# module.net
KiCad netlist of a schematic drawn in EAGLE
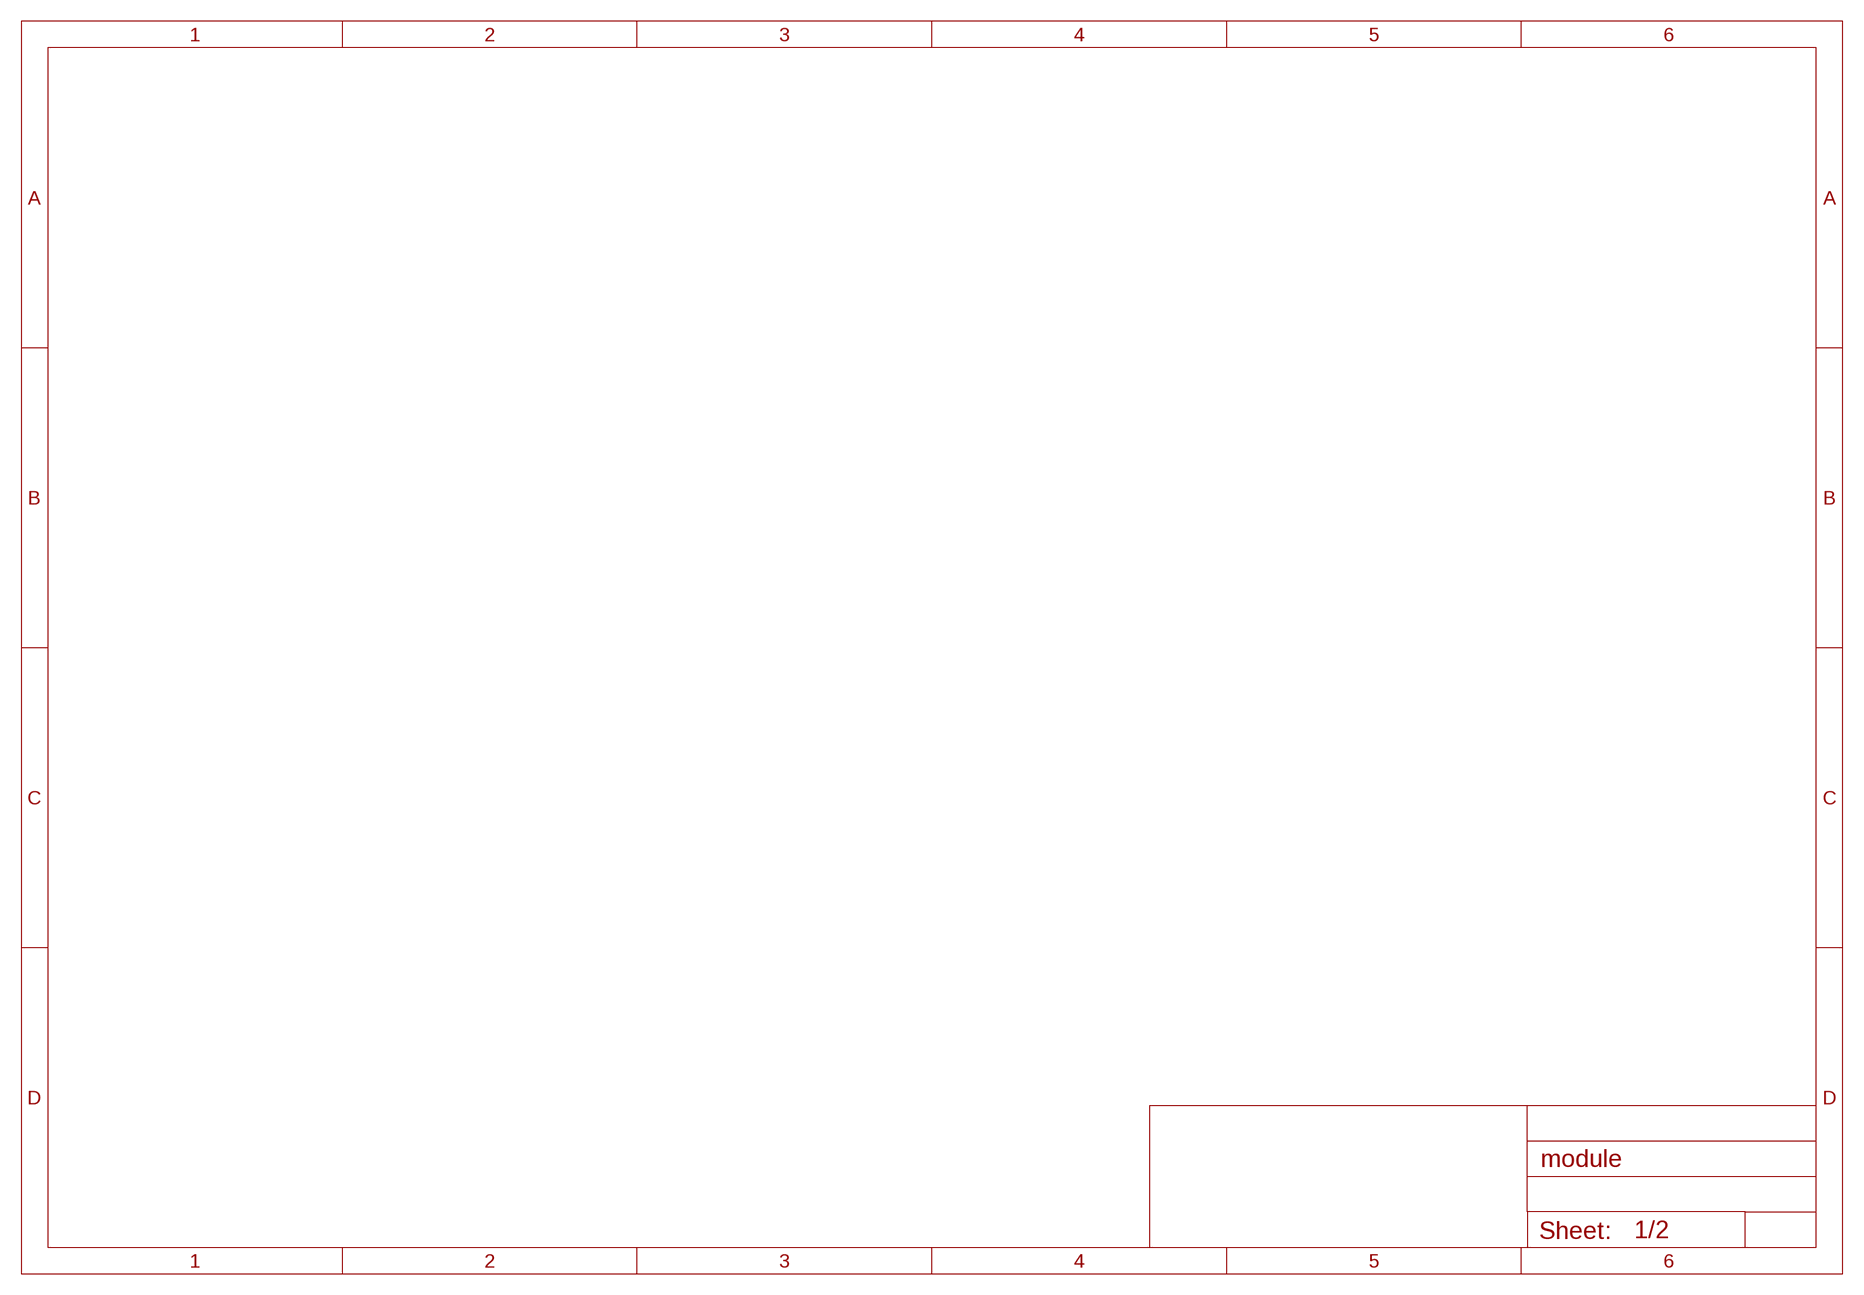
[diagram p0: schematic, sheet 1]
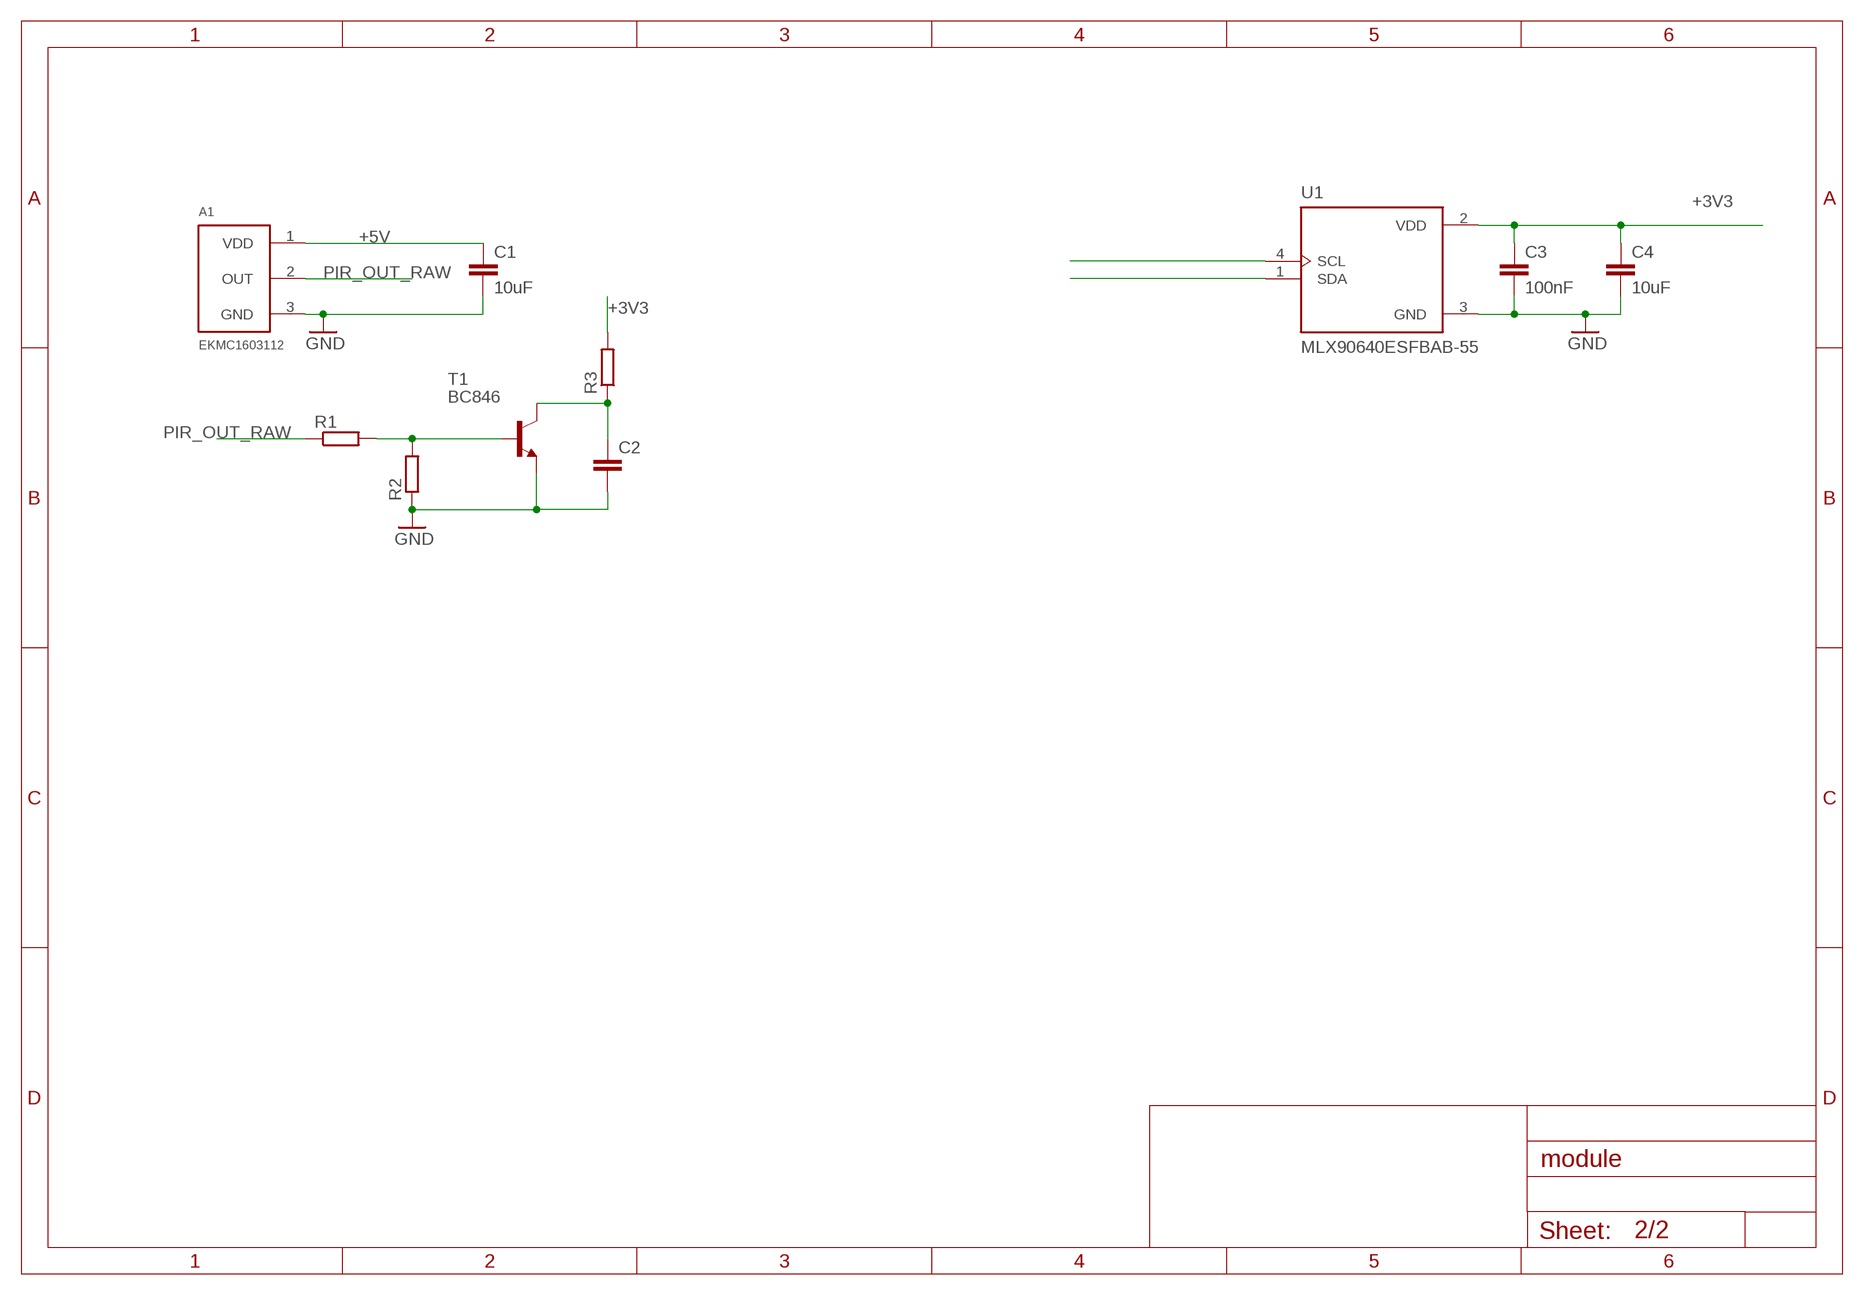
[diagram p1: schematic, sheet 2]

(export (version "E")
  (design (tool "Eeschema 10.0.6"))
  (components
    (comp (ref "A1")
      (value "EKMC1603112")
      (footprint "eagle-import:TO254P2200H2020-3")
      (fields (field (name "MF") "Panasonic Electric"))
      (libsource (lib "eagle-import") (part "EKMC1603112"))
    )
    (comp (ref "C1")
      (value "10uF")
      (footprint "eagle-import:C0805")
      (libsource (lib "eagle-import") (part "C-EUC0805"))
    )
    (comp (ref "C2")
      (value "C-EUC0603")
      (footprint "eagle-import:C0603")
      (libsource (lib "eagle-import") (part "C-EUC0603"))
    )
    (comp (ref "C3")
      (value "100nF")
      (footprint "eagle-import:C0603")
      (libsource (lib "eagle-import") (part "C-EUC0603"))
    )
    (comp (ref "C4")
      (value "10uF")
      (footprint "eagle-import:C0805")
      (libsource (lib "eagle-import") (part "C-EUC0805"))
    )
    (comp (ref "R1")
      (value "R-EU_R0603")
      (footprint "eagle-import:R0603")
      (libsource (lib "eagle-import") (part "R-EU_R0603"))
    )
    (comp (ref "R2")
      (value "R-EU_R0603")
      (footprint "eagle-import:R0603")
      (libsource (lib "eagle-import") (part "R-EU_R0603"))
    )
    (comp (ref "R3")
      (value "R-EU_R0603")
      (footprint "eagle-import:R0603")
      (libsource (lib "eagle-import") (part "R-EU_R0603"))
    )
    (comp (ref "T1")
      (value "BC846")
      (footprint "eagle-import:SOT23")
      (libsource (lib "eagle-import") (part "BC846"))
    )
    (comp (ref "U1")
      (value "MLX90640ESFBAB-55")
      (footprint "eagle-import:TO292-55")
      (libsource (lib "eagle-import") (part "MLX90640ESFBAB-55"))
    )
  )
  (nets
    (net (code "1") (name "+3V3") (class "Default")
      (node (ref "C3") (pin "1") (pinfunction "1_1") (pintype "passive"))
      (node (ref "C4") (pin "1") (pinfunction "1_1") (pintype "passive"))
      (node (ref "R3") (pin "2") (pinfunction "2_2") (pintype "passive"))
      (node (ref "U1") (pin "2") (pinfunction "VDD_2") (pintype "power_in"))
    )
    (net (code "2") (name "+5V") (class "Default")
      (node (ref "A1") (pin "1") (pinfunction "VDD_1") (pintype "power_in"))
      (node (ref "C1") (pin "1") (pinfunction "1_1") (pintype "passive"))
    )
    (net (code "3") (name "GND") (class "Default")
      (node (ref "A1") (pin "3") (pinfunction "GND_3") (pintype "power_in"))
      (node (ref "C1") (pin "2") (pinfunction "2_2") (pintype "passive"))
      (node (ref "C2") (pin "2") (pinfunction "2_2") (pintype "passive"))
      (node (ref "C3") (pin "2") (pinfunction "2_2") (pintype "passive"))
      (node (ref "C4") (pin "2") (pinfunction "2_2") (pintype "passive"))
      (node (ref "R2") (pin "1") (pinfunction "1_1") (pintype "passive"))
      (node (ref "T1") (pin "2") (pinfunction "E_2") (pintype "passive"))
      (node (ref "U1") (pin "3") (pinfunction "GND_3") (pintype "power_in"))
    )
    (net (code "4") (name "Net-(T1-B)") (class "Default")
      (node (ref "R1") (pin "2") (pinfunction "2_2") (pintype "passive"))
      (node (ref "R2") (pin "2") (pinfunction "2_2") (pintype "passive"))
      (node (ref "T1") (pin "1") (pinfunction "B_1") (pintype "passive"))
    )
    (net (code "5") (name "Net-(T1-C)") (class "Default")
      (node (ref "C2") (pin "1") (pinfunction "1_1") (pintype "passive"))
      (node (ref "R3") (pin "1") (pinfunction "1_1") (pintype "passive"))
      (node (ref "T1") (pin "3") (pinfunction "C_3") (pintype "passive"))
    )
    (net (code "6") (name "PIR_OUT_RAW") (class "Default")
      (node (ref "A1") (pin "2") (pinfunction "OUT_2") (pintype "output"))
      (node (ref "R1") (pin "1") (pinfunction "1_1") (pintype "passive"))
    )
    (net (code "7") (name "unconnected-(U1-SCL-Pad4)") (class "Default")
      (node (ref "U1") (pin "4") (pinfunction "SCL_4") (pintype "input"))
    )
    (net (code "8") (name "unconnected-(U1-SDA-Pad1)") (class "Default")
      (node (ref "U1") (pin "1") (pinfunction "SDA_1") (pintype "bidirectional"))
    )
  )
)
